# SHDN-BSPD-S06-V00-BSPDSense.net
KiCad netlist of a schematic drawn in Altium Designer
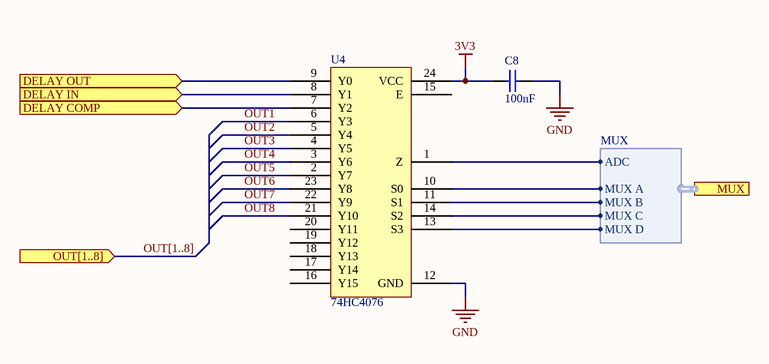
[diagram p0: SHDN-BSPD-S06-V00-BSPDSense.SchDoc]

(export (version "E")
  (design (tool "Eeschema 10.0.6"))
  (components
    (comp (ref "C8")
      (value "100nF")
      (footprint "Cap_Ceramic_0603")
      (description "Capacitor, Ceramic, SMD, 100nF, 50V, 5%, X7R, 0603")
      (libsource (lib "StandardCapacitors") (part "100nF 50V 5% X7R 0603"))
    )
    (comp (ref "U4")
      (value "74HC4076")
      (footprint "TSSOP-24")
      (description "16:1 Analog Switch (SP16T) 60Ohm, TSSOP24")
      (libsource (lib "QUTMS_MuliplexerLibrary") (part "74HC4076"))
    )
  )
  (nets
    (net (code "2") (name "/ADC") (class "Default")
      (node (ref "U4") (pin "1") (pinfunction "Z_1") (pintype "passive"))
    )
    (net (code "3") (name "/DELAY COMP") (class "Default")
      (node (ref "U4") (pin "7") (pinfunction "Y2_7") (pintype "passive"))
    )
    (net (code "4") (name "/DELAY IN") (class "Default")
      (node (ref "U4") (pin "8") (pinfunction "Y1_8") (pintype "passive"))
    )
    (net (code "5") (name "/DELAY OUT") (class "Default")
      (node (ref "U4") (pin "9") (pinfunction "Y0_9") (pintype "passive"))
    )
    (net (code "6") (name "/MUX A") (class "Default")
      (node (ref "U4") (pin "10") (pinfunction "S0_10") (pintype "passive"))
    )
    (net (code "7") (name "/MUX B") (class "Default")
      (node (ref "U4") (pin "11") (pinfunction "S1_11") (pintype "passive"))
    )
    (net (code "8") (name "/MUX C") (class "Default")
      (node (ref "U4") (pin "14") (pinfunction "S2_14") (pintype "passive"))
    )
    (net (code "9") (name "/MUX D") (class "Default")
      (node (ref "U4") (pin "13") (pinfunction "S3_13") (pintype "passive"))
    )
    (net (code "10") (name "/OUT1") (class "Default")
      (node (ref "U4") (pin "6") (pinfunction "Y3_6") (pintype "passive"))
    )
    (net (code "11") (name "/OUT2") (class "Default")
      (node (ref "U4") (pin "5") (pinfunction "Y4_5") (pintype "passive"))
    )
    (net (code "12") (name "/OUT3") (class "Default")
      (node (ref "U4") (pin "4") (pinfunction "Y5_4") (pintype "passive"))
    )
    (net (code "13") (name "/OUT4") (class "Default")
      (node (ref "U4") (pin "3") (pinfunction "Y6_3") (pintype "passive"))
    )
    (net (code "14") (name "/OUT5") (class "Default")
      (node (ref "U4") (pin "2") (pinfunction "Y7_2") (pintype "passive"))
    )
    (net (code "15") (name "/OUT6") (class "Default")
      (node (ref "U4") (pin "23") (pinfunction "Y8_23") (pintype "passive"))
    )
    (net (code "16") (name "/OUT7") (class "Default")
      (node (ref "U4") (pin "22") (pinfunction "Y9_22") (pintype "passive"))
    )
    (net (code "17") (name "/OUT8") (class "Default")
      (node (ref "U4") (pin "21") (pinfunction "Y10_21") (pintype "passive"))
    )
    (net (code "20") (name "3V3") (class "Default")
      (node (ref "C8") (pin "1") (pinfunction "1_1") (pintype "passive"))
      (node (ref "U4") (pin "24") (pinfunction "VCC_24") (pintype "passive"))
    )
    (net (code "21") (name "GND") (class "Default")
      (node (ref "C8") (pin "2") (pinfunction "2_2") (pintype "passive"))
      (node (ref "U4") (pin "12") (pinfunction "GND_12") (pintype "passive"))
    )
    (net (code "22") (name "unconnected-(U4-E-Pad15)") (class "Default")
      (node (ref "U4") (pin "15") (pinfunction "E_15") (pintype "passive"))
    )
    (net (code "23") (name "unconnected-(U4-Y11-Pad20)") (class "Default")
      (node (ref "U4") (pin "20") (pinfunction "Y11_20") (pintype "passive"))
    )
    (net (code "24") (name "unconnected-(U4-Y12-Pad19)") (class "Default")
      (node (ref "U4") (pin "19") (pinfunction "Y12_19") (pintype "passive"))
    )
    (net (code "25") (name "unconnected-(U4-Y13-Pad18)") (class "Default")
      (node (ref "U4") (pin "18") (pinfunction "Y13_18") (pintype "passive"))
    )
    (net (code "26") (name "unconnected-(U4-Y14-Pad17)") (class "Default")
      (node (ref "U4") (pin "17") (pinfunction "Y14_17") (pintype "passive"))
    )
    (net (code "27") (name "unconnected-(U4-Y15-Pad16)") (class "Default")
      (node (ref "U4") (pin "16") (pinfunction "Y15_16") (pintype "passive"))
    )
  )
)
